# 24V_Power.net
KiCad netlist of a schematic drawn in Altium Designer
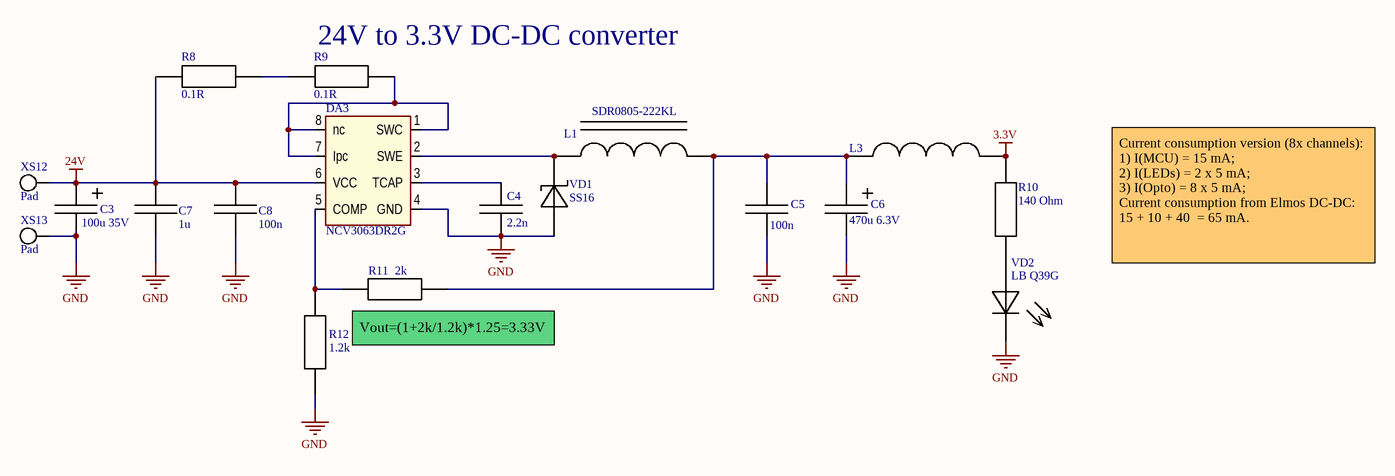
[diagram p0: 24V_Power.SchDoc]

(export (version "E")
  (design (tool "Eeschema 10.0.6"))
  (components
    (comp (ref "C3")
      (value "100u 35V")
      (footprint "C8*12-3.5")
      (description "Capasitor")
      (libsource (lib "24V_Power") (part "100u 35V"))
    )
    (comp (ref "C4")
      (value "2.2n")
      (footprint "C0603")
      (description "Capasitor 0603")
      (libsource (lib "24V_Power") (part "2.2n"))
    )
    (comp (ref "C5")
      (value "100n")
      (footprint "C0603")
      (description "Capasitor 0603")
      (libsource (lib "24V_Power") (part "100n"))
    )
    (comp (ref "C6")
      (value "470u 6.3V")
      (footprint "C6.3*11-2.5")
      (description "Capasitor")
      (libsource (lib "24V_Power") (part "470u 6.3V"))
    )
    (comp (ref "C7")
      (value "1u")
      (footprint "C1206")
      (description "Capasitor 1206")
      (libsource (lib "24V_Power") (part "1u"))
    )
    (comp (ref "C8")
      (value "100n")
      (footprint "C0603")
      (description "Capasitor 0603")
      (libsource (lib "24V_Power") (part "100n"))
    )
    (comp (ref "DA3")
      (value "NCV3063DR2G")
      (footprint "SOIC-8 NB")
      (description "1.5 A, ADJ, Step-Up/Down/\r\nInverting Switching\r\nRegulators, SOIC-8")
      (libsource (lib "24V_Power") (part "NCV3063DR2G"))
    )
    (comp (ref "L1")
      (value "SDR0805-222KL")
      (footprint "SDR0805")
      (description "SMD Power Inductor")
      (libsource (lib "24V_Power") (part "2200uH"))
    )
    (comp (ref "L3")
      (value "BLM21PG331SN1D")
      (footprint "INDC2012X08N")
      (description "Ferrite bead smd")
      (libsource (lib "24V_Power") (part "BLM21PG331SN1D"))
    )
    (comp (ref "R8")
      (value "0.1R")
      (footprint "R1206")
      (description "Reisitor 1206")
      (libsource (lib "24V_Power") (part "0.1R"))
    )
    (comp (ref "R9")
      (value "0.1R")
      (footprint "R1206")
      (description "Reisitor 1206")
      (libsource (lib "24V_Power") (part "0.1R"))
    )
    (comp (ref "R10")
      (value "140 Ohm")
      (footprint "R0603")
      (description "Resistor 0603")
      (libsource (lib "MCU") (part "140 Ohm"))
    )
    (comp (ref "R11")
      (value "2k")
      (footprint "R0603")
      (description "Resistor 0603")
      (libsource (lib "24V_Power") (part "2k"))
    )
    (comp (ref "R12")
      (value "1.2k")
      (footprint "R0603")
      (description "Resistor 0603")
      (libsource (lib "24V_Power") (part "1.2k"))
    )
    (comp (ref "VD1")
      (value "SS16")
      (footprint "shotci")
      (description "Surface Mount Schottky Barrier Rectifier")
      (libsource (lib "24V_Power") (part "SS16"))
    )
    (comp (ref "VD2")
      (value "LB Q39G")
      (footprint "0603D_R")
      (description "Power Led")
      (libsource (lib "24V_Power") (part "RED_LED"))
    )
    (comp (ref "XS12")
      (value "Pad")
      (footprint "LOTPAD")
      (description "PCB TH Pad")
      (libsource (lib "Nolden_Power_Board_V2") (part "Pad"))
    )
    (comp (ref "XS13")
      (value "Pad")
      (footprint "LOTPAD")
      (description "PCB TH Pad")
      (libsource (lib "Nolden_Power_Board_V2") (part "Pad"))
    )
  )
  (nets
    (net (code "1") (name "3.3V") (class "Default")
      (node (ref "L3") (pin "2") (pinfunction "2_2") (pintype "passive"))
      (node (ref "R10") (pin "2") (pinfunction "2_2") (pintype "passive"))
    )
    (net (code "2") (name "24V") (class "Default")
      (node (ref "C3") (pin "1") (pinfunction "1_1") (pintype "passive"))
      (node (ref "C7") (pin "2") (pinfunction "2_2") (pintype "passive"))
      (node (ref "C8") (pin "2") (pinfunction "2_2") (pintype "passive"))
      (node (ref "DA3") (pin "6") (pinfunction "VCC_6") (pintype "passive"))
      (node (ref "R8") (pin "1") (pinfunction "1_1") (pintype "passive"))
      (node (ref "XS12") (pin "1") (pinfunction "1_1") (pintype "passive"))
    )
    (net (code "3") (name "GND") (class "Default")
      (node (ref "C3") (pin "2") (pinfunction "2_2") (pintype "passive"))
      (node (ref "C4") (pin "1") (pinfunction "1_1") (pintype "passive"))
      (node (ref "C5") (pin "1") (pinfunction "1_1") (pintype "passive"))
      (node (ref "C6") (pin "2") (pinfunction "2_2") (pintype "passive"))
      (node (ref "C7") (pin "1") (pinfunction "1_1") (pintype "passive"))
      (node (ref "C8") (pin "1") (pinfunction "1_1") (pintype "passive"))
      (node (ref "DA3") (pin "4") (pinfunction "GND_4") (pintype "passive"))
      (node (ref "R12") (pin "1") (pinfunction "1_1") (pintype "passive"))
      (node (ref "VD1") (pin "1") (pinfunction "А_1") (pintype "passive"))
      (node (ref "VD2") (pin "2") (pinfunction "К_2") (pintype "passive"))
      (node (ref "XS13") (pin "1") (pinfunction "1_1") (pintype "passive"))
    )
    (net (code "4") (name "Net-(C5-Pad2)") (class "Default")
      (node (ref "C5") (pin "2") (pinfunction "2_2") (pintype "passive"))
      (node (ref "C6") (pin "1") (pinfunction "1_1") (pintype "passive"))
      (node (ref "L1") (pin "2") (pinfunction "2_2") (pintype "passive"))
      (node (ref "L3") (pin "1") (pinfunction "1_1") (pintype "passive"))
      (node (ref "R11") (pin "2") (pinfunction "2_2") (pintype "passive"))
    )
    (net (code "5") (name "Net-(DA3-COMP)") (class "Default")
      (node (ref "DA3") (pin "5") (pinfunction "COMP_5") (pintype "passive"))
      (node (ref "R11") (pin "1") (pinfunction "1_1") (pintype "passive"))
      (node (ref "R12") (pin "2") (pinfunction "2_2") (pintype "passive"))
    )
    (net (code "6") (name "Net-(DA3-Ipc)") (class "Default")
      (node (ref "DA3") (pin "1") (pinfunction "SWC_1") (pintype "passive"))
      (node (ref "DA3") (pin "7") (pinfunction "Ipc_7") (pintype "passive"))
      (node (ref "DA3") (pin "8") (pinfunction "nc_8") (pintype "passive"))
      (node (ref "R9") (pin "2") (pinfunction "2_2") (pintype "passive"))
    )
    (net (code "7") (name "Net-(DA3-SWE)") (class "Default")
      (node (ref "DA3") (pin "2") (pinfunction "SWE_2") (pintype "passive"))
      (node (ref "L1") (pin "1") (pinfunction "1_1") (pintype "passive"))
      (node (ref "VD1") (pin "2") (pinfunction "К_2") (pintype "passive"))
    )
    (net (code "8") (name "Net-(DA3-TCAP)") (class "Default")
      (node (ref "C4") (pin "2") (pinfunction "2_2") (pintype "passive"))
      (node (ref "DA3") (pin "3") (pinfunction "TCAP_3") (pintype "passive"))
    )
    (net (code "9") (name "Net-(R8-Pad2)") (class "Default")
      (node (ref "R8") (pin "2") (pinfunction "2_2") (pintype "passive"))
      (node (ref "R9") (pin "1") (pinfunction "1_1") (pintype "passive"))
    )
    (net (code "10") (name "Net-(VD2-А)") (class "Default")
      (node (ref "R10") (pin "1") (pinfunction "1_1") (pintype "passive"))
      (node (ref "VD2") (pin "1") (pinfunction "А_1") (pintype "passive"))
    )
  )
)
